# bike_meter.net
KiCad netlist of a schematic drawn in EasyEDA
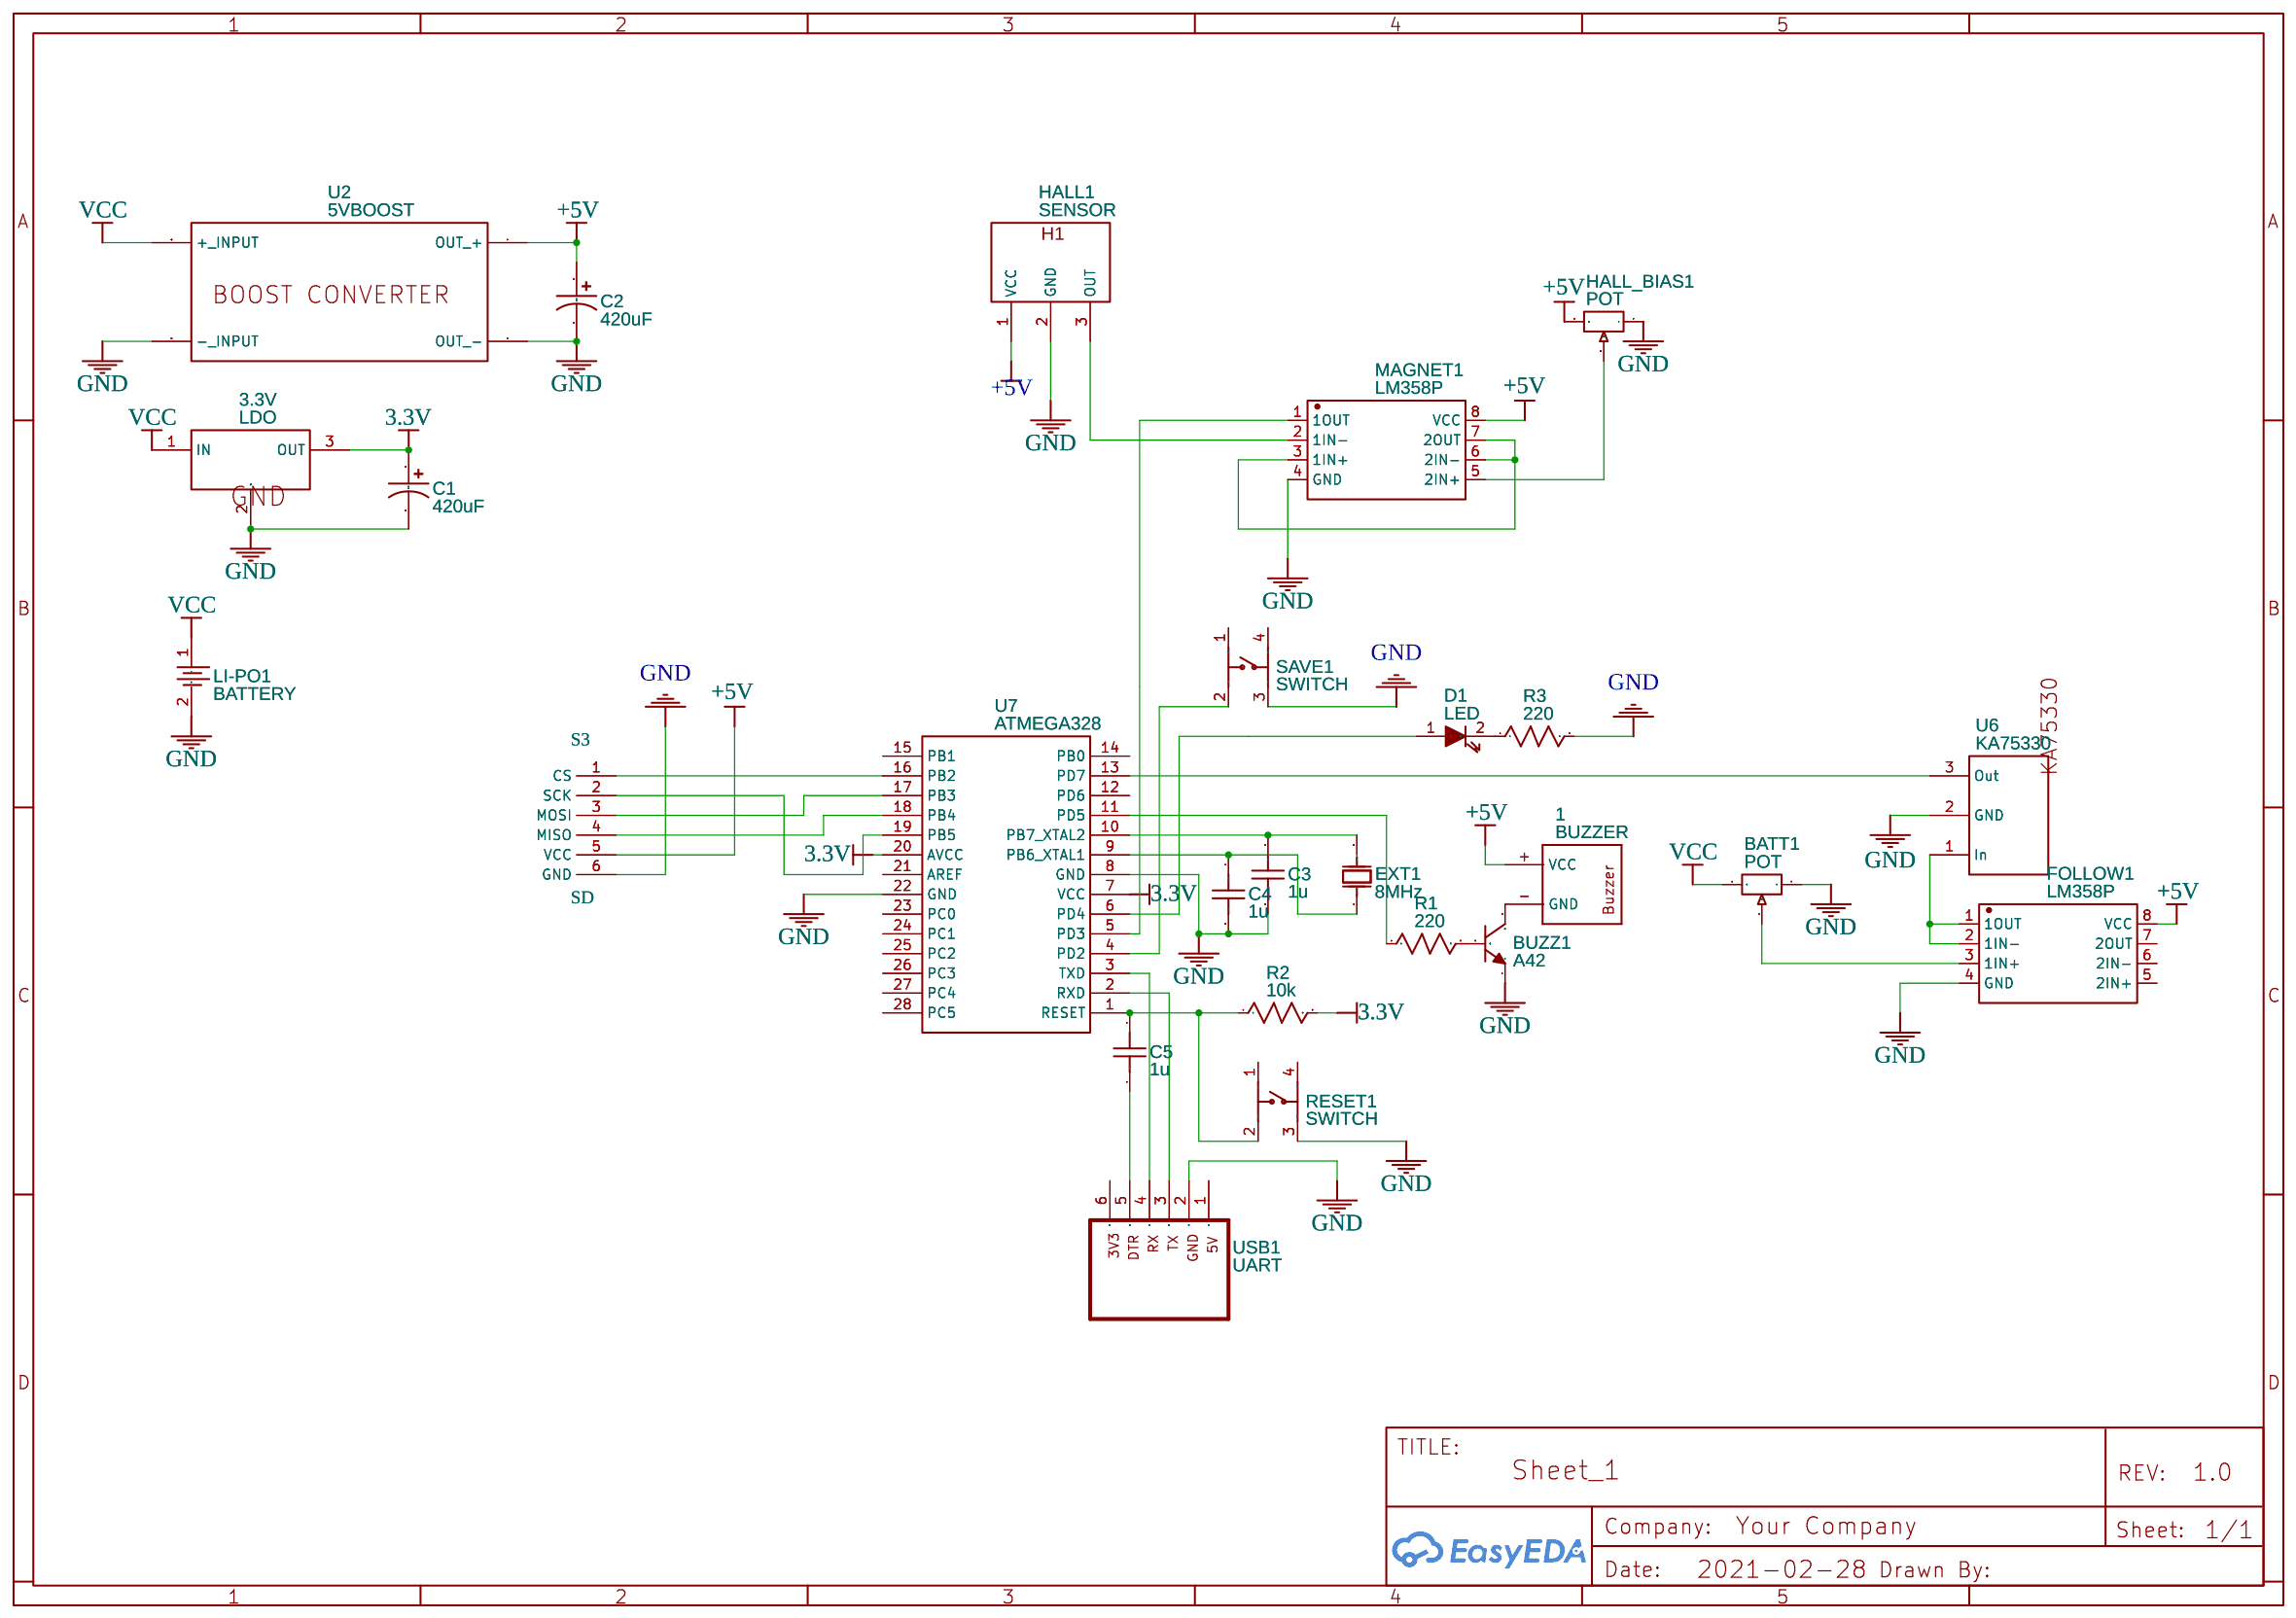
[diagram p0: schematic sheet]

(export (version "E")
  (design (tool "Eeschema 10.0.6"))
  (components
    (comp (ref "1") (value "BUZZER") (libsource (lib "") (part "BUZZER")))
    (comp (ref "3.3V")
      (value "LDO")
      (fields (field (name "BOM_Manufacturer Part") "CJ78L05") (field (name "BOM_Supplier Part") "C2079"))
      (libsource (lib "") (part "7805(SOT-89)"))
    )
    (comp (ref "BATT1") (value "POT") (libsource (lib "") (part "R_3386P_EU_1")))
    (comp (ref "BUZZ1")
      (value "A42")
      (fields
        (field (name "BOM_Manufacturer Part") "2n3904S-RTK/PS")
        (field (name "BOM_Supplier Part") "C18536")
      )
      (libsource (lib "") (part "2N3904(SOT-23)"))
    )
    (comp (ref "C1") (value "420uF") (libsource (lib "") (part "CE_TH_D10.0×F5.0_US_1")))
    (comp (ref "C2") (value "420uF") (libsource (lib "") (part "CE_TH_D10.0×F5.0_US")))
    (comp (ref "C3") (value "1u") (libsource (lib "") (part "C_RAD-0.3_US")))
    (comp (ref "C4") (value "1u") (libsource (lib "") (part "C_RAD-0.3_US")))
    (comp (ref "C5") (value "1u") (libsource (lib "") (part "C_RAD-0.3_US")))
    (comp (ref "D1") (value "LED") (libsource (lib "") (part "LED")))
    (comp (ref "EXT1")
      (value "8MHz")
      (fields
        (field (name "BOM_Manufacturer Part") "7A-8.000MAAE-T")
        (field (name "BOM_Supplier Part") "717-7A-8.000MAAE-T")
      )
      (libsource (lib "") (part "NX5032GA-8MHZ(STD-CSK-7)"))
    )
    (comp (ref "FOLLOW1")
      (value "LM358P")
      (fields (field (name "BOM_Supplier Part") "C5213"))
      (libsource (lib "") (part "LM358P_1"))
    )
    (comp (ref "HALL1") (value "SENSOR") (libsource (lib "") (part "hall")))
    (comp (ref "HALL_BIAS1") (value "POT") (libsource (lib "") (part "R_3386P_EU")))
    (comp (ref "LI-PO1")
      (value "BATTERY")
      (fields (field (name "BOM_Manufacturer Part") "CR1220-2") (field (name "BOM_Supplier Part") "C70381"))
      (libsource (lib "") (part "CR1220-2"))
    )
    (comp (ref "MAGNET1")
      (value "LM358P")
      (fields (field (name "BOM_Supplier Part") "C5213"))
      (libsource (lib "") (part "LM358P"))
    )
    (comp (ref "R1") (value "220") (libsource (lib "") (part "R_0603_US")))
    (comp (ref "R2") (value "10k") (libsource (lib "") (part "R_0603_US")))
    (comp (ref "R3") (value "220") (libsource (lib "") (part "R_0603_US")))
    (comp (ref "RESET1")
      (value "SWITCH")
      (fields
        (field (name "BOM_Manufacturer Part") "button6*6*8")
        (field (name "BOM_Supplier Part") "C59982")
      )
      (libsource (lib "") (part "button6*6*8"))
    )
    (comp (ref "S3") (value "SD") (libsource (lib "") (part "Unknown_280_-400")))
    (comp (ref "SAVE1")
      (value "SWITCH")
      (fields
        (field (name "BOM_Manufacturer Part") "button6*6*8")
        (field (name "BOM_Supplier Part") "C59982")
      )
      (libsource (lib "") (part "button6*6*8_1"))
    )
    (comp (ref "U2")
      (value "5VBOOST")
      (fields (field (name "BOM_Manufacturer Part") "New SchematicLib"))
      (libsource (lib "") (part "boostyconverter"))
    )
    (comp (ref "U6") (value "KA75330") (libsource (lib "") (part "KA75330")))
    (comp (ref "U7")
      (value "ATMEGA328")
      (fields
        (field (name "BOM_Manufacturer Part") "ATMEGA328P-PU")
        (field (name "BOM_Supplier Part") "C33901")
      )
      (libsource (lib "") (part "ATMEGA328"))
    )
    (comp (ref "USB1") (value "UART") (libsource (lib "") (part "UART")))
  )
  (nets
    (net (code "1") (name "+5V") (class "Default")
      (node (ref "1") (pin "+") (pinfunction "VCC_+") (pintype "bidirectional"))
      (node (ref "C2") (pin "1") (pinfunction "1_1") (pintype "unspecified"))
      (node (ref "FOLLOW1") (pin "8") (pinfunction "VCC_8") (pintype "unspecified"))
      (node (ref "HALL1") (pin "1") (pinfunction "VCC_1") (pintype "unspecified"))
      (node (ref "HALL_BIAS1") (pin "3") (pinfunction "3_3") (pintype "input"))
      (node (ref "MAGNET1") (pin "8") (pinfunction "VCC_8") (pintype "unspecified"))
      (node (ref "S3") (pin "5") (pinfunction "VCC_5") (pintype "unspecified"))
      (node (ref "U2") (pin "1") (pinfunction "OUT_+_1") (pintype "unspecified"))
    )
    (net (code "2") (name "3.3V") (class "Default")
      (node (ref "3.3V") (pin "3") (pinfunction "OUT_3") (pintype "passive"))
      (node (ref "C1") (pin "1") (pinfunction "1_1") (pintype "unspecified"))
      (node (ref "R2") (pin "2") (pinfunction "2_2") (pintype "unspecified"))
      (node (ref "U7") (pin "20") (pinfunction "AVCC_20") (pintype "passive"))
      (node (ref "U7") (pin "7") (pinfunction "VCC_7") (pintype "passive"))
    )
    (net (code "3") (name "GND") (class "Default")
      (node (ref "3.3V") (pin "2") (pinfunction "GND_2") (pintype "passive"))
      (node (ref "BATT1") (pin "1") (pinfunction "1_1") (pintype "input"))
      (node (ref "BUZZ1") (pin "1") (pinfunction "E_1") (pintype "input"))
      (node (ref "C1") (pin "2") (pinfunction "2_2") (pintype "unspecified"))
      (node (ref "C2") (pin "2") (pinfunction "2_2") (pintype "unspecified"))
      (node (ref "C3") (pin "2") (pinfunction "2_2") (pintype "unspecified"))
      (node (ref "C4") (pin "2") (pinfunction "2_2") (pintype "unspecified"))
      (node (ref "FOLLOW1") (pin "4") (pinfunction "GND_4") (pintype "unspecified"))
      (node (ref "HALL1") (pin "2") (pinfunction "GND_2") (pintype "unspecified"))
      (node (ref "HALL_BIAS1") (pin "1") (pinfunction "1_1") (pintype "input"))
      (node (ref "LI-PO1") (pin "2") (pinfunction "2_2") (pintype "input"))
      (node (ref "MAGNET1") (pin "4") (pinfunction "GND_4") (pintype "unspecified"))
      (node (ref "R3") (pin "2") (pinfunction "2_2") (pintype "unspecified"))
      (node (ref "RESET1") (pin "3") (pinfunction "3_3") (pintype "unspecified"))
      (node (ref "S3") (pin "6") (pinfunction "GND_6") (pintype "unspecified"))
      (node (ref "SAVE1") (pin "3") (pinfunction "3_3") (pintype "unspecified"))
      (node (ref "U2") (pin "4") (pinfunction "OUT_-_4") (pintype "unspecified"))
      (node (ref "U2") (pin "6") (pinfunction "-_INPUT_6") (pintype "unspecified"))
      (node (ref "U6") (pin "2") (pinfunction "GND_2") (pintype "unspecified"))
      (node (ref "U7") (pin "22") (pinfunction "GND_22") (pintype "passive"))
      (node (ref "U7") (pin "8") (pinfunction "GND_8") (pintype "passive"))
      (node (ref "USB1") (pin "2") (pinfunction "2_2") (pintype "unspecified"))
    )
    (net (code "4") (name "Net-(1-GND)") (class "Default")
      (node (ref "1") (pin "-") (pinfunction "GND_-") (pintype "bidirectional"))
      (node (ref "BUZZ1") (pin "3") (pinfunction "C_3") (pintype "input"))
    )
    (net (code "5") (name "Net-(BUZZ1-B)") (class "Default")
      (node (ref "BUZZ1") (pin "2") (pinfunction "B_2") (pintype "input"))
      (node (ref "R1") (pin "2") (pinfunction "2_2") (pintype "unspecified"))
    )
    (net (code "6") (name "Net-(C5-Pad2)") (class "Default")
      (node (ref "C5") (pin "2") (pinfunction "2_2") (pintype "unspecified"))
      (node (ref "USB1") (pin "5") (pinfunction "5_5") (pintype "unspecified"))
    )
    (net (code "7") (name "Net-(D1-A)") (class "Default")
      (node (ref "D1") (pin "1") (pinfunction "A_1") (pintype "unspecified"))
      (node (ref "U7") (pin "6") (pinfunction "PD4_6") (pintype "bidirectional"))
    )
    (net (code "8") (name "Net-(D1-K)") (class "Default")
      (node (ref "D1") (pin "2") (pinfunction "K_2") (pintype "unspecified"))
      (node (ref "R3") (pin "1") (pinfunction "1_1") (pintype "unspecified"))
    )
    (net (code "9") (name "Net-(EXT1-OSC1)") (class "Default")
      (node (ref "C4") (pin "1") (pinfunction "1_1") (pintype "unspecified"))
      (node (ref "EXT1") (pin "1") (pinfunction "OSC1_1") (pintype "unspecified"))
      (node (ref "U7") (pin "9") (pinfunction "PB6_XTAL1_9") (pintype "bidirectional"))
    )
    (net (code "10") (name "Net-(EXT1-OSC2)") (class "Default")
      (node (ref "C3") (pin "1") (pinfunction "1_1") (pintype "unspecified"))
      (node (ref "EXT1") (pin "2") (pinfunction "OSC2_2") (pintype "unspecified"))
      (node (ref "U7") (pin "10") (pinfunction "PB7_XTAL2_10") (pintype "bidirectional"))
    )
    (net (code "11") (name "Net-(FOLLOW1-1IN+)") (class "Default")
      (node (ref "BATT1") (pin "2") (pinfunction "2_2") (pintype "input"))
      (node (ref "FOLLOW1") (pin "3") (pinfunction "1IN+_3") (pintype "unspecified"))
    )
    (net (code "12") (name "Net-(FOLLOW1-1IN-)") (class "Default")
      (node (ref "FOLLOW1") (pin "1") (pinfunction "1OUT_1") (pintype "unspecified"))
      (node (ref "FOLLOW1") (pin "2") (pinfunction "1IN-_2") (pintype "unspecified"))
      (node (ref "U6") (pin "1") (pinfunction "In_1") (pintype "unspecified"))
    )
    (net (code "13") (name "Net-(HALL1-OUT)") (class "Default")
      (node (ref "HALL1") (pin "3") (pinfunction "OUT_3") (pintype "unspecified"))
      (node (ref "MAGNET1") (pin "2") (pinfunction "1IN-_2") (pintype "unspecified"))
    )
    (net (code "14") (name "Net-(MAGNET1-1IN+)") (class "Default")
      (node (ref "MAGNET1") (pin "3") (pinfunction "1IN+_3") (pintype "unspecified"))
      (node (ref "MAGNET1") (pin "6") (pinfunction "2IN-_6") (pintype "unspecified"))
      (node (ref "MAGNET1") (pin "7") (pinfunction "2OUT_7") (pintype "unspecified"))
    )
    (net (code "15") (name "Net-(MAGNET1-1OUT)") (class "Default")
      (node (ref "MAGNET1") (pin "1") (pinfunction "1OUT_1") (pintype "unspecified"))
      (node (ref "U7") (pin "5") (pinfunction "PD3_5") (pintype "bidirectional"))
    )
    (net (code "16") (name "Net-(MAGNET1-2IN+)") (class "Default")
      (node (ref "HALL_BIAS1") (pin "2") (pinfunction "2_2") (pintype "input"))
      (node (ref "MAGNET1") (pin "5") (pinfunction "2IN+_5") (pintype "unspecified"))
    )
    (net (code "17") (name "Net-(S3-CS)") (class "Default")
      (node (ref "S3") (pin "1") (pinfunction "CS_1") (pintype "unspecified"))
      (node (ref "U7") (pin "16") (pinfunction "PB2_16") (pintype "bidirectional"))
    )
    (net (code "18") (name "Net-(S3-MISO)") (class "Default")
      (node (ref "S3") (pin "4") (pinfunction "MISO_4") (pintype "unspecified"))
      (node (ref "U7") (pin "18") (pinfunction "PB4_18") (pintype "bidirectional"))
    )
    (net (code "19") (name "Net-(S3-MOSI)") (class "Default")
      (node (ref "S3") (pin "3") (pinfunction "MOSI_3") (pintype "unspecified"))
      (node (ref "U7") (pin "17") (pinfunction "PB3_17") (pintype "bidirectional"))
    )
    (net (code "20") (name "Net-(S3-SCK)") (class "Default")
      (node (ref "S3") (pin "2") (pinfunction "SCK_2") (pintype "unspecified"))
      (node (ref "U7") (pin "19") (pinfunction "PB5_19") (pintype "bidirectional"))
    )
    (net (code "21") (name "Net-(U6-Out)") (class "Default")
      (node (ref "U6") (pin "3") (pinfunction "Out_3") (pintype "unspecified"))
      (node (ref "U7") (pin "13") (pinfunction "PD7_13") (pintype "bidirectional"))
    )
    (net (code "22") (name "Net-(U7-PD2)") (class "Default")
      (node (ref "SAVE1") (pin "2") (pinfunction "2_2") (pintype "unspecified"))
      (node (ref "U7") (pin "4") (pinfunction "PD2_4") (pintype "bidirectional"))
    )
    (net (code "23") (name "Net-(U7-PD5)") (class "Default")
      (node (ref "R1") (pin "1") (pinfunction "1_1") (pintype "unspecified"))
      (node (ref "U7") (pin "11") (pinfunction "PD5_11") (pintype "bidirectional"))
    )
    (net (code "24") (name "Net-(U7-RESET)") (class "Default")
      (node (ref "C5") (pin "1") (pinfunction "1_1") (pintype "unspecified"))
      (node (ref "R2") (pin "1") (pinfunction "1_1") (pintype "unspecified"))
      (node (ref "RESET1") (pin "2") (pinfunction "2_2") (pintype "unspecified"))
      (node (ref "U7") (pin "1") (pinfunction "RESET_1") (pintype "bidirectional"))
    )
    (net (code "25") (name "Net-(U7-RXD)") (class "Default")
      (node (ref "U7") (pin "2") (pinfunction "RXD_2") (pintype "bidirectional"))
      (node (ref "USB1") (pin "3") (pinfunction "3_3") (pintype "unspecified"))
    )
    (net (code "26") (name "Net-(U7-TXD)") (class "Default")
      (node (ref "U7") (pin "3") (pinfunction "TXD_3") (pintype "bidirectional"))
      (node (ref "USB1") (pin "4") (pinfunction "4_4") (pintype "unspecified"))
    )
    (net (code "27") (name "VCC") (class "Default")
      (node (ref "3.3V") (pin "1") (pinfunction "IN_1") (pintype "passive"))
      (node (ref "BATT1") (pin "3") (pinfunction "3_3") (pintype "input"))
      (node (ref "LI-PO1") (pin "1") (pinfunction "1_1") (pintype "input"))
      (node (ref "U2") (pin "5") (pinfunction "+_INPUT_5") (pintype "unspecified"))
    )
    (net (code "28") (name "unconnected-(FOLLOW1-2IN+-Pad5)") (class "Default")
      (node (ref "FOLLOW1") (pin "5") (pinfunction "2IN+_5") (pintype "unspecified"))
    )
    (net (code "29") (name "unconnected-(FOLLOW1-2IN--Pad6)") (class "Default")
      (node (ref "FOLLOW1") (pin "6") (pinfunction "2IN-_6") (pintype "unspecified"))
    )
    (net (code "30") (name "unconnected-(FOLLOW1-2OUT-Pad7)") (class "Default")
      (node (ref "FOLLOW1") (pin "7") (pinfunction "2OUT_7") (pintype "unspecified"))
    )
    (net (code "31") (name "unconnected-(RESET1-Pad1)") (class "Default")
      (node (ref "RESET1") (pin "1") (pinfunction "1_1") (pintype "unspecified"))
    )
    (net (code "32") (name "unconnected-(RESET1-Pad4)") (class "Default")
      (node (ref "RESET1") (pin "4") (pinfunction "4_4") (pintype "unspecified"))
    )
    (net (code "33") (name "unconnected-(SAVE1-Pad1)") (class "Default")
      (node (ref "SAVE1") (pin "1") (pinfunction "1_1") (pintype "unspecified"))
    )
    (net (code "34") (name "unconnected-(SAVE1-Pad4)") (class "Default")
      (node (ref "SAVE1") (pin "4") (pinfunction "4_4") (pintype "unspecified"))
    )
    (net (code "35") (name "unconnected-(U7-AREF-Pad21)") (class "Default")
      (node (ref "U7") (pin "21") (pinfunction "AREF_21") (pintype "passive"))
    )
    (net (code "36") (name "unconnected-(U7-PB0-Pad14)") (class "Default")
      (node (ref "U7") (pin "14") (pinfunction "PB0_14") (pintype "bidirectional"))
    )
    (net (code "37") (name "unconnected-(U7-PB1-Pad15)") (class "Default")
      (node (ref "U7") (pin "15") (pinfunction "PB1_15") (pintype "bidirectional"))
    )
    (net (code "38") (name "unconnected-(U7-PC0-Pad23)") (class "Default")
      (node (ref "U7") (pin "23") (pinfunction "PC0_23") (pintype "bidirectional"))
    )
    (net (code "39") (name "unconnected-(U7-PC1-Pad24)") (class "Default")
      (node (ref "U7") (pin "24") (pinfunction "PC1_24") (pintype "bidirectional"))
    )
    (net (code "40") (name "unconnected-(U7-PC2-Pad25)") (class "Default")
      (node (ref "U7") (pin "25") (pinfunction "PC2_25") (pintype "bidirectional"))
    )
    (net (code "41") (name "unconnected-(U7-PC3-Pad26)") (class "Default")
      (node (ref "U7") (pin "26") (pinfunction "PC3_26") (pintype "bidirectional"))
    )
    (net (code "42") (name "unconnected-(U7-PC4-Pad27)") (class "Default")
      (node (ref "U7") (pin "27") (pinfunction "PC4_27") (pintype "bidirectional"))
    )
    (net (code "43") (name "unconnected-(U7-PC5-Pad28)") (class "Default")
      (node (ref "U7") (pin "28") (pinfunction "PC5_28") (pintype "bidirectional"))
    )
    (net (code "44") (name "unconnected-(U7-PD6-Pad12)") (class "Default")
      (node (ref "U7") (pin "12") (pinfunction "PD6_12") (pintype "bidirectional"))
    )
    (net (code "45") (name "unconnected-(USB1-Pad1)") (class "Default")
      (node (ref "USB1") (pin "1") (pinfunction "1_1") (pintype "unspecified"))
    )
    (net (code "46") (name "unconnected-(USB1-Pad6)") (class "Default")
      (node (ref "USB1") (pin "6") (pinfunction "6_6") (pintype "unspecified"))
    )
  )
)
